# VoltimetroDigital.net
KiCad netlist of a schematic drawn in EAGLE
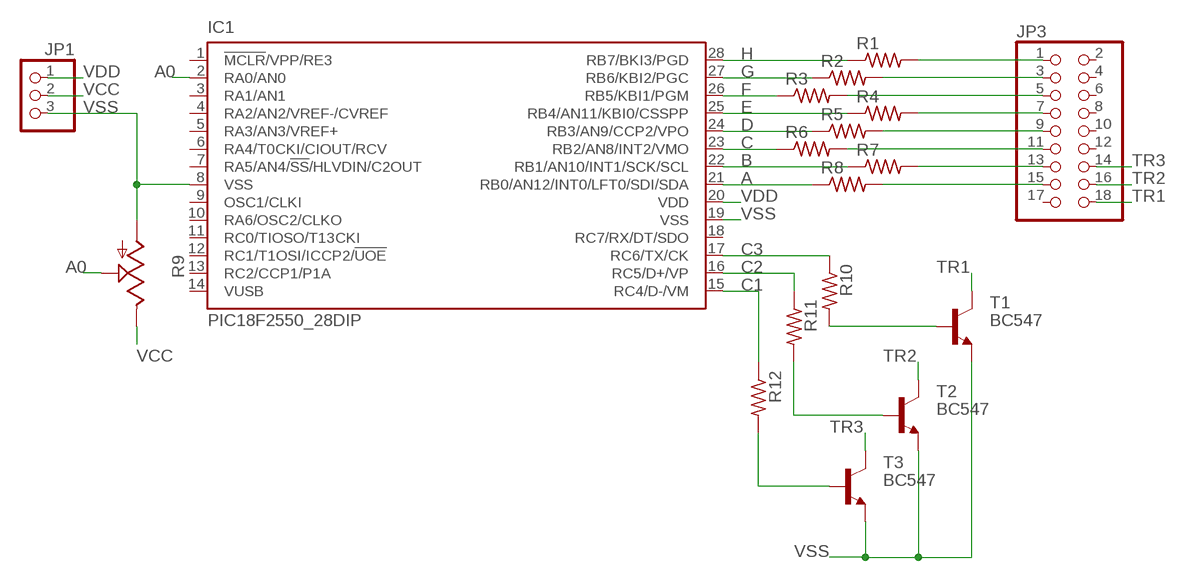
[diagram p0: schematic, sheet 1]

(export (version "E")
  (design (tool "Eeschema 10.0.6"))
  (components
    (comp (ref "IC1")
      (value "PIC18F2550_28DIP")
      (footprint "eagle-import:DIL28-3")
      (fields (field (name "MF") "MICROCHIP") (field (name "MPN") "PIC18F2550-I/SP"))
      (libsource (lib "eagle-import") (part "PIC18F2_28DIP550"))
    )
    (comp (ref "JP1")
      (value "PINHD-1X3")
      (footprint "eagle-import:1X03")
      (libsource (lib "eagle-import") (part "PINHD-1X3"))
    )
    (comp (ref "JP3")
      (value "PINHD-2X9")
      (footprint "eagle-import:2X09")
      (libsource (lib "eagle-import") (part "PINHD-2X9"))
    )
    (comp (ref "R1")
      (value "R-US_0204/7")
      (footprint "eagle-import:0204_7")
      (libsource (lib "eagle-import") (part "R-US_0204/7"))
    )
    (comp (ref "R2")
      (value "R-US_0204/7")
      (footprint "eagle-import:0204_7")
      (libsource (lib "eagle-import") (part "R-US_0204/7"))
    )
    (comp (ref "R3")
      (value "R-US_0204/7")
      (footprint "eagle-import:0204_7")
      (libsource (lib "eagle-import") (part "R-US_0204/7"))
    )
    (comp (ref "R4")
      (value "R-US_0204/7")
      (footprint "eagle-import:0204_7")
      (libsource (lib "eagle-import") (part "R-US_0204/7"))
    )
    (comp (ref "R5")
      (value "R-US_0204/7")
      (footprint "eagle-import:0204_7")
      (libsource (lib "eagle-import") (part "R-US_0204/7"))
    )
    (comp (ref "R6")
      (value "R-US_0204/7")
      (footprint "eagle-import:0204_7")
      (libsource (lib "eagle-import") (part "R-US_0204/7"))
    )
    (comp (ref "R7")
      (value "R-US_0204/7")
      (footprint "eagle-import:0204_7")
      (libsource (lib "eagle-import") (part "R-US_0204/7"))
    )
    (comp (ref "R8")
      (value "R-US_0204/7")
      (footprint "eagle-import:0204_7")
      (libsource (lib "eagle-import") (part "R-US_0204/7"))
    )
    (comp (ref "R9")
      (value "TRIM_US-LI10")
      (footprint "eagle-import:LI10")
      (libsource (lib "eagle-import") (part "TRIM_US-LI10"))
    )
    (comp (ref "R10")
      (value "R-US_0204/7")
      (footprint "eagle-import:0204_7")
      (libsource (lib "eagle-import") (part "R-US_0204/7"))
    )
    (comp (ref "R11")
      (value "R-US_0204/7")
      (footprint "eagle-import:0204_7")
      (libsource (lib "eagle-import") (part "R-US_0204/7"))
    )
    (comp (ref "R12")
      (value "R-US_0204/7")
      (footprint "eagle-import:0204_7")
      (libsource (lib "eagle-import") (part "R-US_0204/7"))
    )
    (comp (ref "T1")
      (value "BC547")
      (footprint "eagle-import:TO92")
      (libsource (lib "eagle-import") (part "BC547"))
    )
    (comp (ref "T2")
      (value "BC547")
      (footprint "eagle-import:TO92")
      (libsource (lib "eagle-import") (part "BC547"))
    )
    (comp (ref "T3")
      (value "BC547")
      (footprint "eagle-import:TO92")
      (libsource (lib "eagle-import") (part "BC547"))
    )
  )
  (nets
    (net (code "1") (name "/A") (class "Default")
      (node (ref "IC1") (pin "21") (pinfunction "RB0/AN12/INT0/LFT0/SDI/SDA_21") (pintype "bidirectional"))
      (node (ref "R8") (pin "1") (pinfunction "1_1") (pintype "passive"))
    )
    (net (code "2") (name "/A0") (class "Default")
      (node (ref "IC1") (pin "2") (pinfunction "RA0/AN0_2") (pintype "bidirectional"))
      (node (ref "R9") (pin "S") (pinfunction "S_S") (pintype "passive"))
    )
    (net (code "3") (name "/B") (class "Default")
      (node (ref "IC1") (pin "22") (pinfunction "RB1/AN10/INT1/SCK/SCL_22") (pintype "bidirectional"))
      (node (ref "R7") (pin "1") (pinfunction "1_1") (pintype "passive"))
    )
    (net (code "4") (name "/C") (class "Default")
      (node (ref "IC1") (pin "23") (pinfunction "RB2/AN8/INT2/VMO_23") (pintype "bidirectional"))
      (node (ref "R6") (pin "1") (pinfunction "1_1") (pintype "passive"))
    )
    (net (code "5") (name "/C1") (class "Default")
      (node (ref "IC1") (pin "15") (pinfunction "RC4/D-/VM_15") (pintype "bidirectional"))
      (node (ref "R12") (pin "1") (pinfunction "1_1") (pintype "passive"))
    )
    (net (code "6") (name "/C2") (class "Default")
      (node (ref "IC1") (pin "16") (pinfunction "RC5/D+/VP_16") (pintype "bidirectional"))
      (node (ref "R11") (pin "1") (pinfunction "1_1") (pintype "passive"))
    )
    (net (code "7") (name "/C3") (class "Default")
      (node (ref "IC1") (pin "17") (pinfunction "RC6/TX/CK_17") (pintype "bidirectional"))
      (node (ref "R10") (pin "1") (pinfunction "1_1") (pintype "passive"))
    )
    (net (code "8") (name "/D") (class "Default")
      (node (ref "IC1") (pin "24") (pinfunction "RB3/AN9/CCP2/VPO_24") (pintype "bidirectional"))
      (node (ref "R5") (pin "1") (pinfunction "1_1") (pintype "passive"))
    )
    (net (code "9") (name "/E") (class "Default")
      (node (ref "IC1") (pin "25") (pinfunction "RB4/AN11/KBI0/CSSPP_25") (pintype "bidirectional"))
      (node (ref "R4") (pin "1") (pinfunction "1_1") (pintype "passive"))
    )
    (net (code "10") (name "/F") (class "Default")
      (node (ref "IC1") (pin "26") (pinfunction "RB5/KBI1/PGM_26") (pintype "bidirectional"))
      (node (ref "R3") (pin "1") (pinfunction "1_1") (pintype "passive"))
    )
    (net (code "11") (name "/G") (class "Default")
      (node (ref "IC1") (pin "27") (pinfunction "RB6/KBI2/PGC_27") (pintype "bidirectional"))
      (node (ref "R2") (pin "1") (pinfunction "1_1") (pintype "passive"))
    )
    (net (code "12") (name "/H") (class "Default")
      (node (ref "IC1") (pin "28") (pinfunction "RB7/BKI3/PGD_28") (pintype "bidirectional"))
      (node (ref "R1") (pin "1") (pinfunction "1_1") (pintype "passive"))
    )
    (net (code "13") (name "/TR1") (class "Default")
      (node (ref "JP3") (pin "18") (pinfunction "18_18") (pintype "passive"))
      (node (ref "T1") (pin "3") (pinfunction "C_3") (pintype "passive"))
    )
    (net (code "14") (name "/TR2") (class "Default")
      (node (ref "JP3") (pin "16") (pinfunction "16_16") (pintype "passive"))
      (node (ref "T2") (pin "3") (pinfunction "C_3") (pintype "passive"))
    )
    (net (code "15") (name "/TR3") (class "Default")
      (node (ref "JP3") (pin "14") (pinfunction "14_14") (pintype "passive"))
      (node (ref "T3") (pin "3") (pinfunction "C_3") (pintype "passive"))
    )
    (net (code "16") (name "/VCC") (class "Default")
      (node (ref "JP1") (pin "2") (pinfunction "2_2") (pintype "passive"))
      (node (ref "R9") (pin "E") (pinfunction "E_E") (pintype "passive"))
    )
    (net (code "17") (name "/VDD") (class "Default")
      (node (ref "IC1") (pin "20") (pinfunction "VDD_20") (pintype "power_in"))
      (node (ref "JP1") (pin "1") (pinfunction "1_1") (pintype "passive"))
    )
    (net (code "18") (name "/VSS") (class "Default")
      (node (ref "IC1") (pin "19") (pinfunction "VSS_19") (pintype "power_in"))
      (node (ref "IC1") (pin "8") (pinfunction "VSS_8") (pintype "power_in"))
      (node (ref "JP1") (pin "3") (pinfunction "3_3") (pintype "passive"))
      (node (ref "R9") (pin "A") (pinfunction "A_A") (pintype "passive"))
      (node (ref "T1") (pin "1") (pinfunction "E_1") (pintype "passive"))
      (node (ref "T2") (pin "1") (pinfunction "E_1") (pintype "passive"))
      (node (ref "T3") (pin "1") (pinfunction "E_1") (pintype "passive"))
    )
    (net (code "19") (name "Net-(JP3-Pad1)") (class "Default")
      (node (ref "JP3") (pin "1") (pinfunction "1_1") (pintype "passive"))
      (node (ref "R1") (pin "2") (pinfunction "2_2") (pintype "passive"))
    )
    (net (code "20") (name "Net-(JP3-Pad3)") (class "Default")
      (node (ref "JP3") (pin "3") (pinfunction "3_3") (pintype "passive"))
      (node (ref "R2") (pin "2") (pinfunction "2_2") (pintype "passive"))
    )
    (net (code "21") (name "Net-(JP3-Pad5)") (class "Default")
      (node (ref "JP3") (pin "5") (pinfunction "5_5") (pintype "passive"))
      (node (ref "R3") (pin "2") (pinfunction "2_2") (pintype "passive"))
    )
    (net (code "22") (name "Net-(JP3-Pad7)") (class "Default")
      (node (ref "JP3") (pin "7") (pinfunction "7_7") (pintype "passive"))
      (node (ref "R4") (pin "2") (pinfunction "2_2") (pintype "passive"))
    )
    (net (code "23") (name "Net-(JP3-Pad9)") (class "Default")
      (node (ref "JP3") (pin "9") (pinfunction "9_9") (pintype "passive"))
      (node (ref "R5") (pin "2") (pinfunction "2_2") (pintype "passive"))
    )
    (net (code "24") (name "Net-(JP3-Pad11)") (class "Default")
      (node (ref "JP3") (pin "11") (pinfunction "11_11") (pintype "passive"))
      (node (ref "R6") (pin "2") (pinfunction "2_2") (pintype "passive"))
    )
    (net (code "25") (name "Net-(JP3-Pad13)") (class "Default")
      (node (ref "JP3") (pin "13") (pinfunction "13_13") (pintype "passive"))
      (node (ref "R7") (pin "2") (pinfunction "2_2") (pintype "passive"))
    )
    (net (code "26") (name "Net-(JP3-Pad15)") (class "Default")
      (node (ref "JP3") (pin "15") (pinfunction "15_15") (pintype "passive"))
      (node (ref "R8") (pin "2") (pinfunction "2_2") (pintype "passive"))
    )
    (net (code "27") (name "Net-(T1-B)") (class "Default")
      (node (ref "R10") (pin "2") (pinfunction "2_2") (pintype "passive"))
      (node (ref "T1") (pin "2") (pinfunction "B_2") (pintype "passive"))
    )
    (net (code "28") (name "Net-(T2-B)") (class "Default")
      (node (ref "R11") (pin "2") (pinfunction "2_2") (pintype "passive"))
      (node (ref "T2") (pin "2") (pinfunction "B_2") (pintype "passive"))
    )
    (net (code "29") (name "Net-(T3-B)") (class "Default")
      (node (ref "R12") (pin "2") (pinfunction "2_2") (pintype "passive"))
      (node (ref "T3") (pin "2") (pinfunction "B_2") (pintype "passive"))
    )
    (net (code "30") (name "unconnected-(IC1-OSC1{slash}CLKI-Pad9)") (class "Default")
      (node (ref "IC1") (pin "9") (pinfunction "OSC1/CLKI_9") (pintype "input"))
    )
    (net (code "31") (name "unconnected-(IC1-RA1{slash}AN1-Pad3)") (class "Default")
      (node (ref "IC1") (pin "3") (pinfunction "RA1/AN1_3") (pintype "bidirectional"))
    )
    (net (code "32") (name "unconnected-(IC1-RA2{slash}AN2{slash}VREF-{slash}CVREF-Pad4)") (class "Default")
      (node (ref "IC1") (pin "4") (pinfunction "RA2/AN2/VREF-/CVREF_4") (pintype "bidirectional"))
    )
    (net (code "33") (name "unconnected-(IC1-RA3{slash}AN3{slash}VREF+-Pad5)") (class "Default")
      (node (ref "IC1") (pin "5") (pinfunction "RA3/AN3/VREF+_5") (pintype "bidirectional"))
    )
    (net (code "34") (name "unconnected-(IC1-RA4{slash}T0CKI{slash}CIOUT{slash}RCV-Pad6)") (class "Default")
      (node (ref "IC1") (pin "6") (pinfunction "RA4/T0CKI/CIOUT/RCV_6") (pintype "bidirectional"))
    )
    (net (code "35") (name "unconnected-(IC1-RA5{slash}AN4{slash}~{SS}{slash}HLVDIN{slash}C2OUT-Pad7)") (class "Default")
      (node (ref "IC1") (pin "7") (pinfunction "RA5/AN4/~{SS}/HLVDIN/C2OUT_7") (pintype "bidirectional"))
    )
    (net (code "36") (name "unconnected-(IC1-RA6{slash}OSC2{slash}CLKO-Pad10)") (class "Default")
      (node (ref "IC1") (pin "10") (pinfunction "RA6/OSC2/CLKO_10") (pintype "output"))
    )
    (net (code "37") (name "unconnected-(IC1-RC0{slash}TIOSO{slash}T13CKI-Pad11)") (class "Default")
      (node (ref "IC1") (pin "11") (pinfunction "RC0/TIOSO/T13CKI_11") (pintype "bidirectional"))
    )
    (net (code "38") (name "unconnected-(IC1-RC1{slash}T1OSI{slash}ICCP2{slash}~{UOE}-Pad12)") (class "Default")
      (node (ref "IC1") (pin "12") (pinfunction "RC1/T1OSI/ICCP2/~{UOE}_12") (pintype "bidirectional"))
    )
    (net (code "39") (name "unconnected-(IC1-RC2{slash}CCP1{slash}P1A-Pad13)") (class "Default")
      (node (ref "IC1") (pin "13") (pinfunction "RC2/CCP1/P1A_13") (pintype "bidirectional"))
    )
    (net (code "40") (name "unconnected-(IC1-RC7{slash}RX{slash}DT{slash}SDO-Pad18)") (class "Default")
      (node (ref "IC1") (pin "18") (pinfunction "RC7/RX/DT/SDO_18") (pintype "bidirectional"))
    )
    (net (code "41") (name "unconnected-(IC1-VUSB-Pad14)") (class "Default")
      (node (ref "IC1") (pin "14") (pinfunction "VUSB_14") (pintype "bidirectional"))
    )
    (net (code "42") (name "unconnected-(IC1-~{MCLR}{slash}VPP{slash}RE3-Pad1)") (class "Default")
      (node (ref "IC1") (pin "1") (pinfunction "~{MCLR}/VPP/RE3_1") (pintype "input"))
    )
    (net (code "43") (name "unconnected-(JP3-Pad2)") (class "Default")
      (node (ref "JP3") (pin "2") (pinfunction "2_2") (pintype "passive"))
    )
    (net (code "44") (name "unconnected-(JP3-Pad4)") (class "Default")
      (node (ref "JP3") (pin "4") (pinfunction "4_4") (pintype "passive"))
    )
    (net (code "45") (name "unconnected-(JP3-Pad6)") (class "Default")
      (node (ref "JP3") (pin "6") (pinfunction "6_6") (pintype "passive"))
    )
    (net (code "46") (name "unconnected-(JP3-Pad8)") (class "Default")
      (node (ref "JP3") (pin "8") (pinfunction "8_8") (pintype "passive"))
    )
    (net (code "47") (name "unconnected-(JP3-Pad10)") (class "Default")
      (node (ref "JP3") (pin "10") (pinfunction "10_10") (pintype "passive"))
    )
    (net (code "48") (name "unconnected-(JP3-Pad12)") (class "Default")
      (node (ref "JP3") (pin "12") (pinfunction "12_12") (pintype "passive"))
    )
    (net (code "49") (name "unconnected-(JP3-Pad17)") (class "Default")
      (node (ref "JP3") (pin "17") (pinfunction "17_17") (pintype "passive"))
    )
  )
)
